# Power.net
KiCad netlist of a schematic drawn in Altium Designer
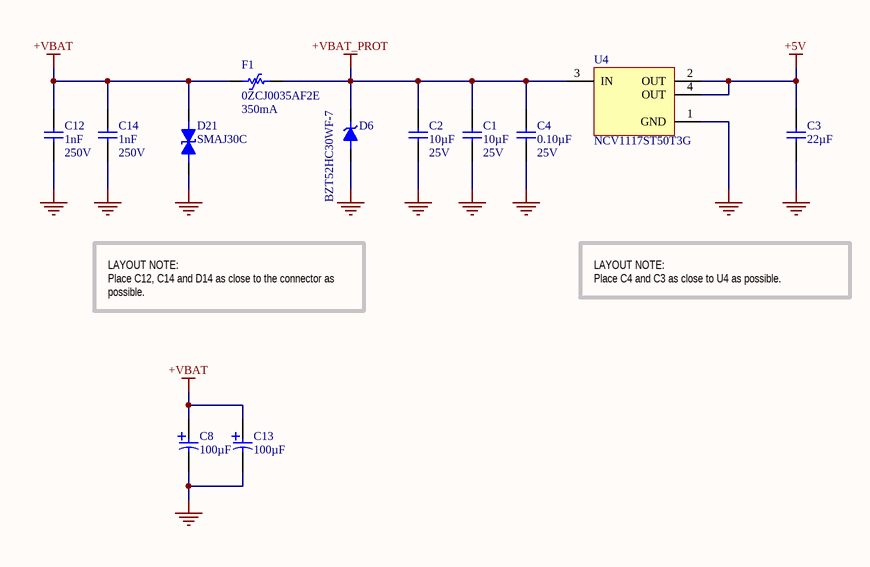
[diagram p0: Power.SchDoc]

(export (version "E")
  (design (tool "Eeschema 10.0.6"))
  (components
    (comp (ref "C1")
      (value "10µF")
      (footprint "CAP-1206-M")
      (fields
        (field (name "PART NUMBER") "CC1206KKX7R8BB106")
        (field (name "TOLERANCE") "±10%")
        (field (name "VOLTAGE") "25V")
        (field (name "MANUFACTURER") "Yageo")
      )
      (libsource (lib "Capacitors") (part "Capacitor"))
    )
    (comp (ref "C2")
      (value "10µF")
      (footprint "CAP-1206-M")
      (fields
        (field (name "PART NUMBER") "CC1206KKX7R8BB106")
        (field (name "TOLERANCE") "±10%")
        (field (name "VOLTAGE") "25V")
        (field (name "MANUFACTURER") "Yageo")
      )
      (libsource (lib "Capacitors") (part "Capacitor"))
    )
    (comp (ref "C3")
      (value "22µF")
      (footprint "CAP-1206-M")
      (fields
        (field (name "PART NUMBER") "CC1206KKX7R6BB226")
        (field (name "TOLERANCE") "±10%")
        (field (name "VOLTAGE") "10V")
      )
      (libsource (lib "Capacitors") (part "Capacitor"))
    )
    (comp (ref "C4")
      (value "0.10µF")
      (footprint "CAP-0402-M")
      (fields
        (field (name "PART NUMBER") "CC0402KRX7R8BB104")
        (field (name "TOLERANCE") "±10%")
        (field (name "VOLTAGE") "25V")
        (field (name "MANUFACTURER") "Yageo")
      )
      (libsource (lib "Capacitors") (part "Capacitor"))
    )
    (comp (ref "C8")
      (value "100µF")
      (footprint "CAPAE7066X80M")
      (fields (field (name "Comment") "EEE-FK1V101XP"))
      (libsource (lib "PDUv2") (part "EEE-FK1V101XP"))
    )
    (comp (ref "C12")
      (value "1nF")
      (footprint "CAP-0805-M")
      (fields
        (field (name "PART NUMBER") "CC0805KRX7RYBB102")
        (field (name "TOLERANCE") "±10%")
        (field (name "VOLTAGE") "250V")
        (field (name "MANUFACTURER") "Yageo")
      )
      (libsource (lib "Capacitors") (part "Capacitor"))
    )
    (comp (ref "C13")
      (value "100µF")
      (footprint "CAPAE7066X80M")
      (fields (field (name "Comment") "EEE-FK1V101XP"))
      (libsource (lib "PDUv2") (part "EEE-FK1V101XP"))
    )
    (comp (ref "C14")
      (value "1nF")
      (footprint "CAP-0805-M")
      (fields
        (field (name "PART NUMBER") "CC0805KRX7RYBB102")
        (field (name "TOLERANCE") "±10%")
        (field (name "VOLTAGE") "250V")
        (field (name "MANUFACTURER") "Yageo")
      )
      (libsource (lib "Capacitors") (part "Capacitor"))
    )
    (comp (ref "D6")
      (value "BZT52HC30WF-7")
      (footprint "SODFL340X115-2N")
      (libsource (lib "PDUv2") (part "BZT52HC30WF-7"))
    )
    (comp (ref "D21")
      (value "SMAJ30C")
      (footprint "SON127P500X135-2N")
      (libsource (lib "PDU-UV17") (part "SMAJ30C"))
    )
    (comp (ref "F1")
      (value "0ZCJ0035AF2E")
      (footprint "0ZCJ-1206-0.9")
      (fields (field (name "ALTIUM_VALUE") "350mA"))
      (libsource (lib "PDU-UV17") (part "0ZCJ0035AF2E"))
    )
    (comp (ref "U4")
      (value "NCV1117ST50T3G")
      (footprint "SOT230P700X180-4N")
      (libsource (lib "PDUv2") (part "NCV1117ST50T3G"))
    )
  )
  (nets
    (net (code "1") (name "+5V") (class "Default")
      (node (ref "C3") (pin "2") (pinfunction "2_2") (pintype "passive"))
      (node (ref "U4") (pin "2") (pinfunction "OUT_2") (pintype "power_in"))
      (node (ref "U4") (pin "4") (pinfunction "OUT_4") (pintype "power_in"))
    )
    (net (code "2") (name "+VBAT") (class "Default")
      (node (ref "C12") (pin "1") (pinfunction "1_1") (pintype "passive"))
      (node (ref "C13") (pin "2") (pinfunction "2_2") (pintype "passive"))
      (node (ref "C14") (pin "1") (pinfunction "1_1") (pintype "passive"))
      (node (ref "C8") (pin "2") (pinfunction "2_2") (pintype "passive"))
      (node (ref "D21") (pin "1") (pinfunction "1_1") (pintype "passive"))
      (node (ref "F1") (pin "1") (pinfunction "1_1") (pintype "passive"))
    )
    (net (code "3") (name "+VBAT_PROT") (class "Default")
      (node (ref "C1") (pin "2") (pinfunction "2_2") (pintype "passive"))
      (node (ref "C2") (pin "2") (pinfunction "2_2") (pintype "passive"))
      (node (ref "C4") (pin "2") (pinfunction "2_2") (pintype "passive"))
      (node (ref "D6") (pin "1") (pinfunction "K_1") (pintype "passive"))
      (node (ref "F1") (pin "2") (pinfunction "2_2") (pintype "passive"))
      (node (ref "U4") (pin "3") (pinfunction "IN_3") (pintype "power_in"))
    )
    (net (code "4") (name "GND") (class "Default")
      (node (ref "C1") (pin "1") (pinfunction "1_1") (pintype "passive"))
      (node (ref "C12") (pin "2") (pinfunction "2_2") (pintype "passive"))
      (node (ref "C13") (pin "1") (pinfunction "1_1") (pintype "passive"))
      (node (ref "C14") (pin "2") (pinfunction "2_2") (pintype "passive"))
      (node (ref "C2") (pin "1") (pinfunction "1_1") (pintype "passive"))
      (node (ref "C3") (pin "1") (pinfunction "1_1") (pintype "passive"))
      (node (ref "C4") (pin "1") (pinfunction "1_1") (pintype "passive"))
      (node (ref "C8") (pin "1") (pinfunction "1_1") (pintype "passive"))
      (node (ref "D21") (pin "2") (pinfunction "2_2") (pintype "passive"))
      (node (ref "D6") (pin "2") (pinfunction "A_2") (pintype "passive"))
      (node (ref "U4") (pin "1") (pinfunction "GND_1") (pintype "passive"))
    )
  )
)
